# ROG_Condor.net
KiCad netlist of a schematic drawn in EAGLE
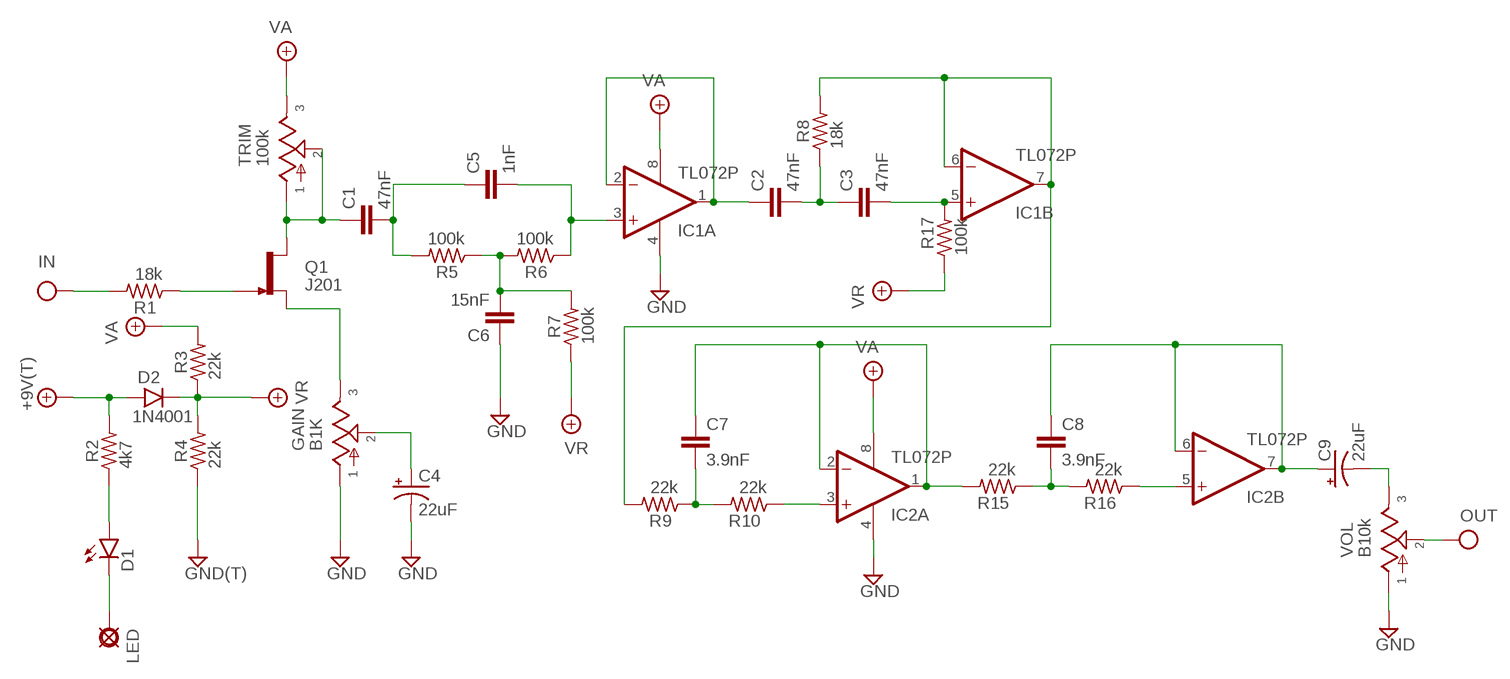
[diagram p0: schematic, sheet 1]

(export (version "E")
  (design (tool "Eeschema 10.0.6"))
  (components
    (comp (ref "+9V")
      (value "+9V(T)")
      (footprint "eagle-import:SQUARE")
      (libsource (lib "eagle-import") (part "+9V(T)"))
    )
    (comp (ref "C1")
      (value "47nF")
      (footprint "eagle-import:075X040")
      (libsource (lib "eagle-import") (part "075X0402"))
    )
    (comp (ref "C2")
      (value "47nF")
      (footprint "eagle-import:075X040")
      (libsource (lib "eagle-import") (part "075X0402"))
    )
    (comp (ref "C3")
      (value "47nF")
      (footprint "eagle-import:075X040")
      (libsource (lib "eagle-import") (part "075X0402"))
    )
    (comp (ref "C4")
      (value "22uF")
      (footprint "eagle-import:050_020_1")
      (libsource (lib "eagle-import") (part "0501"))
    )
    (comp (ref "C5")
      (value "1nF")
      (footprint "eagle-import:075X040")
      (libsource (lib "eagle-import") (part "075X0402"))
    )
    (comp (ref "C6")
      (value "15nF")
      (footprint "eagle-import:075X040")
      (libsource (lib "eagle-import") (part "075X0402"))
    )
    (comp (ref "C7")
      (value "3.9nF")
      (footprint "eagle-import:075X040")
      (libsource (lib "eagle-import") (part "075X0402"))
    )
    (comp (ref "C8")
      (value "3.9nF")
      (footprint "eagle-import:075X040")
      (libsource (lib "eagle-import") (part "075X0402"))
    )
    (comp (ref "C9")
      (value "22uF")
      (footprint "eagle-import:050_020_1")
      (libsource (lib "eagle-import") (part "0501"))
    )
    (comp (ref "D1")
      (value "LED3MM")
      (footprint "eagle-import:LED3MM")
      (libsource (lib "eagle-import") (part "LED3MM"))
    )
    (comp (ref "D2")
      (value "1N4001")
      (footprint "eagle-import:DO41-3")
      (libsource (lib "eagle-import") (part "1N400X.3"))
    )
    (comp (ref "GAIN")
      (value "B1K")
      (footprint "eagle-import:16MM")
      (libsource (lib "eagle-import") (part "POT16MM"))
    )
    (comp (ref "GND")
      (value "GND(T)")
      (footprint "eagle-import:SQUARE")
      (libsource (lib "eagle-import") (part "GND(T)"))
    )
    (comp (ref "IC1")
      (value "TL072P")
      (footprint "eagle-import:DIL08")
      (libsource (lib "eagle-import") (part "TL072P"))
    )
    (comp (ref "IC2")
      (value "TL072P")
      (footprint "eagle-import:DIL08")
      (libsource (lib "eagle-import") (part "TL072P"))
    )
    (comp (ref "IN")
      (value "IN(T)")
      (footprint "eagle-import:SQUARE")
      (libsource (lib "eagle-import") (part "IN(T)"))
    )
    (comp (ref "LED")
      (value "LED")
      (footprint "eagle-import:SQUARE")
      (libsource (lib "eagle-import") (part "PAD"))
    )
    (comp (ref "OUT")
      (value "OUT(T)")
      (footprint "eagle-import:SQUARE")
      (libsource (lib "eagle-import") (part "OUT(T)"))
    )
    (comp (ref "Q1")
      (value "J201")
      (footprint "eagle-import:TO92-")
      (libsource (lib "eagle-import") (part "J201"))
    )
    (comp (ref "R1")
      (value "18k")
      (footprint "eagle-import:R0207_3")
      (libsource (lib "eagle-import") (part "6MM.3"))
    )
    (comp (ref "R2")
      (value "4k7")
      (footprint "eagle-import:R0207_3")
      (libsource (lib "eagle-import") (part "6MM.3"))
    )
    (comp (ref "R3")
      (value "22k")
      (footprint "eagle-import:R0207_3")
      (libsource (lib "eagle-import") (part "6MM.3"))
    )
    (comp (ref "R4")
      (value "22k")
      (footprint "eagle-import:R0207_3")
      (libsource (lib "eagle-import") (part "6MM.3"))
    )
    (comp (ref "R5")
      (value "100k")
      (footprint "eagle-import:R0207_3")
      (libsource (lib "eagle-import") (part "6MM.3"))
    )
    (comp (ref "R6")
      (value "100k")
      (footprint "eagle-import:R0207_3")
      (libsource (lib "eagle-import") (part "6MM.3"))
    )
    (comp (ref "R7")
      (value "100k")
      (footprint "eagle-import:R0207_3")
      (libsource (lib "eagle-import") (part "6MM.3"))
    )
    (comp (ref "R8")
      (value "18k")
      (footprint "eagle-import:R0207_3")
      (libsource (lib "eagle-import") (part "6MM.3"))
    )
    (comp (ref "R9")
      (value "22k")
      (footprint "eagle-import:R0207_3")
      (libsource (lib "eagle-import") (part "6MM.3"))
    )
    (comp (ref "R10")
      (value "22k")
      (footprint "eagle-import:R0207_3")
      (libsource (lib "eagle-import") (part "6MM.3"))
    )
    (comp (ref "R15")
      (value "22k")
      (footprint "eagle-import:R0207_3")
      (libsource (lib "eagle-import") (part "6MM.3"))
    )
    (comp (ref "R16")
      (value "22k")
      (footprint "eagle-import:R0207_3")
      (libsource (lib "eagle-import") (part "6MM.3"))
    )
    (comp (ref "R17")
      (value "100k")
      (footprint "eagle-import:R0207_3")
      (libsource (lib "eagle-import") (part "6MM.3"))
    )
    (comp (ref "TRIM")
      (value "100k")
      (footprint "eagle-import:B25P")
      (libsource (lib "eagle-import") (part "POTTRIM"))
    )
    (comp (ref "VOL")
      (value "B10k")
      (footprint "eagle-import:16MM")
      (libsource (lib "eagle-import") (part "POT16MM"))
    )
  )
  (nets
    (net (code "1") (name "+9V(T)") (class "Default")
      (node (ref "+9V") (pin "1") (pinfunction "+9V_1") (pintype "power_in"))
      (node (ref "D2") (pin "A") (pinfunction "A_A") (pintype "passive"))
      (node (ref "R2") (pin "2") (pinfunction "2_2") (pintype "passive"))
    )
    (net (code "2") (name "GND") (class "Default")
      (node (ref "C4") (pin "-") (pinfunction "-_-") (pintype "passive"))
      (node (ref "C6") (pin "1") (pinfunction "1_1") (pintype "passive"))
      (node (ref "GAIN") (pin "1") (pinfunction "1_1") (pintype "passive"))
      (node (ref "GND") (pin "1") (pinfunction "GND_1") (pintype "power_in"))
      (node (ref "IC1") (pin "4") (pinfunction "V-_4") (pintype "power_in"))
      (node (ref "IC2") (pin "4") (pinfunction "V-_4") (pintype "power_in"))
      (node (ref "R4") (pin "1") (pinfunction "1_1") (pintype "passive"))
      (node (ref "VOL") (pin "1") (pinfunction "1_1") (pintype "passive"))
    )
    (net (code "3") (name "IN(T)") (class "Default")
      (node (ref "IN") (pin "1") (pinfunction "IN_1") (pintype "power_in"))
      (node (ref "R1") (pin "2") (pinfunction "2_2") (pintype "passive"))
    )
    (net (code "4") (name "Net-(C1-Pad2)") (class "Default")
      (node (ref "C1") (pin "2") (pinfunction "2_2") (pintype "passive"))
      (node (ref "C5") (pin "1") (pinfunction "1_1") (pintype "passive"))
      (node (ref "R5") (pin "2") (pinfunction "2_2") (pintype "passive"))
    )
    (net (code "5") (name "Net-(C2-Pad2)") (class "Default")
      (node (ref "C2") (pin "2") (pinfunction "2_2") (pintype "passive"))
      (node (ref "C3") (pin "1") (pinfunction "1_1") (pintype "passive"))
      (node (ref "R8") (pin "1") (pinfunction "1_1") (pintype "passive"))
    )
    (net (code "6") (name "Net-(C4-Pad+)") (class "Default")
      (node (ref "C4") (pin "+") (pinfunction "+_+") (pintype "passive"))
      (node (ref "GAIN") (pin "2") (pinfunction "2_2") (pintype "passive"))
    )
    (net (code "7") (name "Net-(C6-Pad2)") (class "Default")
      (node (ref "C6") (pin "2") (pinfunction "2_2") (pintype "passive"))
      (node (ref "R5") (pin "1") (pinfunction "1_1") (pintype "passive"))
      (node (ref "R6") (pin "2") (pinfunction "2_2") (pintype "passive"))
      (node (ref "R7") (pin "2") (pinfunction "2_2") (pintype "passive"))
    )
    (net (code "8") (name "Net-(C7-Pad2)") (class "Default")
      (node (ref "C7") (pin "2") (pinfunction "2_2") (pintype "passive"))
      (node (ref "R10") (pin "2") (pinfunction "2_2") (pintype "passive"))
      (node (ref "R9") (pin "1") (pinfunction "1_1") (pintype "passive"))
    )
    (net (code "9") (name "Net-(C8-Pad2)") (class "Default")
      (node (ref "C8") (pin "2") (pinfunction "2_2") (pintype "passive"))
      (node (ref "R15") (pin "1") (pinfunction "1_1") (pintype "passive"))
      (node (ref "R16") (pin "2") (pinfunction "2_2") (pintype "passive"))
    )
    (net (code "10") (name "Net-(C9-Pad-)") (class "Default")
      (node (ref "C9") (pin "-") (pinfunction "-_-") (pintype "passive"))
      (node (ref "VOL") (pin "3") (pinfunction "3_3") (pintype "passive"))
    )
    (net (code "11") (name "Net-(D1-C)") (class "Default")
      (node (ref "D1") (pin "K") (pinfunction "C_K") (pintype "passive"))
      (node (ref "LED") (pin "1") (pinfunction "PAD_1") (pintype "passive"))
    )
    (net (code "12") (name "Net-(D1-PadA)") (class "Default")
      (node (ref "D1") (pin "A") (pinfunction "A_A") (pintype "passive"))
      (node (ref "R2") (pin "1") (pinfunction "1_1") (pintype "passive"))
    )
    (net (code "13") (name "Net-(IC1A-+IN)") (class "Default")
      (node (ref "C5") (pin "2") (pinfunction "2_2") (pintype "passive"))
      (node (ref "IC1") (pin "3") (pinfunction "+IN_3") (pintype "input"))
      (node (ref "R6") (pin "1") (pinfunction "1_1") (pintype "passive"))
    )
    (net (code "14") (name "Net-(IC1A--IN)") (class "Default")
      (node (ref "C2") (pin "1") (pinfunction "1_1") (pintype "passive"))
      (node (ref "IC1") (pin "1") (pinfunction "OUT_1") (pintype "output"))
      (node (ref "IC1") (pin "2") (pinfunction "-IN_2") (pintype "input"))
    )
    (net (code "15") (name "Net-(IC1B-+IN)") (class "Default")
      (node (ref "C3") (pin "2") (pinfunction "2_2") (pintype "passive"))
      (node (ref "IC1") (pin "5") (pinfunction "+IN_5") (pintype "input"))
      (node (ref "R17") (pin "2") (pinfunction "2_2") (pintype "passive"))
    )
    (net (code "16") (name "Net-(IC1B--IN)") (class "Default")
      (node (ref "IC1") (pin "6") (pinfunction "-IN_6") (pintype "input"))
      (node (ref "IC1") (pin "7") (pinfunction "OUT_7") (pintype "output"))
      (node (ref "R8") (pin "2") (pinfunction "2_2") (pintype "passive"))
      (node (ref "R9") (pin "2") (pinfunction "2_2") (pintype "passive"))
    )
    (net (code "17") (name "Net-(IC2A-+IN)") (class "Default")
      (node (ref "IC2") (pin "3") (pinfunction "+IN_3") (pintype "input"))
      (node (ref "R10") (pin "1") (pinfunction "1_1") (pintype "passive"))
    )
    (net (code "18") (name "Net-(IC2A--IN)") (class "Default")
      (node (ref "C7") (pin "1") (pinfunction "1_1") (pintype "passive"))
      (node (ref "IC2") (pin "1") (pinfunction "OUT_1") (pintype "output"))
      (node (ref "IC2") (pin "2") (pinfunction "-IN_2") (pintype "input"))
      (node (ref "R15") (pin "2") (pinfunction "2_2") (pintype "passive"))
    )
    (net (code "19") (name "Net-(IC2B-+IN)") (class "Default")
      (node (ref "IC2") (pin "5") (pinfunction "+IN_5") (pintype "input"))
      (node (ref "R16") (pin "1") (pinfunction "1_1") (pintype "passive"))
    )
    (net (code "20") (name "Net-(IC2B--IN)") (class "Default")
      (node (ref "C8") (pin "1") (pinfunction "1_1") (pintype "passive"))
      (node (ref "C9") (pin "+") (pinfunction "+_+") (pintype "passive"))
      (node (ref "IC2") (pin "6") (pinfunction "-IN_6") (pintype "input"))
      (node (ref "IC2") (pin "7") (pinfunction "OUT_7") (pintype "output"))
    )
    (net (code "21") (name "Net-(Q1-D)") (class "Default")
      (node (ref "C1") (pin "1") (pinfunction "1_1") (pintype "passive"))
      (node (ref "Q1") (pin "3") (pinfunction "D_3") (pintype "passive"))
      (node (ref "TRIM") (pin "1") (pinfunction "1_1") (pintype "passive"))
      (node (ref "TRIM") (pin "2") (pinfunction "2_2") (pintype "passive"))
    )
    (net (code "22") (name "Net-(Q1-G)") (class "Default")
      (node (ref "Q1") (pin "1") (pinfunction "G_1") (pintype "passive"))
      (node (ref "R1") (pin "1") (pinfunction "1_1") (pintype "passive"))
    )
    (net (code "23") (name "Net-(Q1-S)") (class "Default")
      (node (ref "GAIN") (pin "3") (pinfunction "3_3") (pintype "passive"))
      (node (ref "Q1") (pin "2") (pinfunction "S_2") (pintype "passive"))
    )
    (net (code "24") (name "OUT(T)") (class "Default")
      (node (ref "OUT") (pin "1") (pinfunction "OUT_1") (pintype "power_in"))
      (node (ref "VOL") (pin "2") (pinfunction "2_2") (pintype "passive"))
    )
    (net (code "25") (name "VA") (class "Default")
      (node (ref "IC1") (pin "8") (pinfunction "V+_8") (pintype "power_in"))
      (node (ref "IC2") (pin "8") (pinfunction "V+_8") (pintype "power_in"))
      (node (ref "R3") (pin "2") (pinfunction "2_2") (pintype "passive"))
      (node (ref "TRIM") (pin "3") (pinfunction "3_3") (pintype "passive"))
    )
    (net (code "26") (name "VR") (class "Default")
      (node (ref "D2") (pin "C") (pinfunction "C_C") (pintype "passive"))
      (node (ref "R17") (pin "1") (pinfunction "1_1") (pintype "passive"))
      (node (ref "R3") (pin "1") (pinfunction "1_1") (pintype "passive"))
      (node (ref "R4") (pin "2") (pinfunction "2_2") (pintype "passive"))
      (node (ref "R7") (pin "1") (pinfunction "1_1") (pintype "passive"))
    )
  )
)
